# racer.net
KiCad netlist of a schematic drawn in Altium Designer
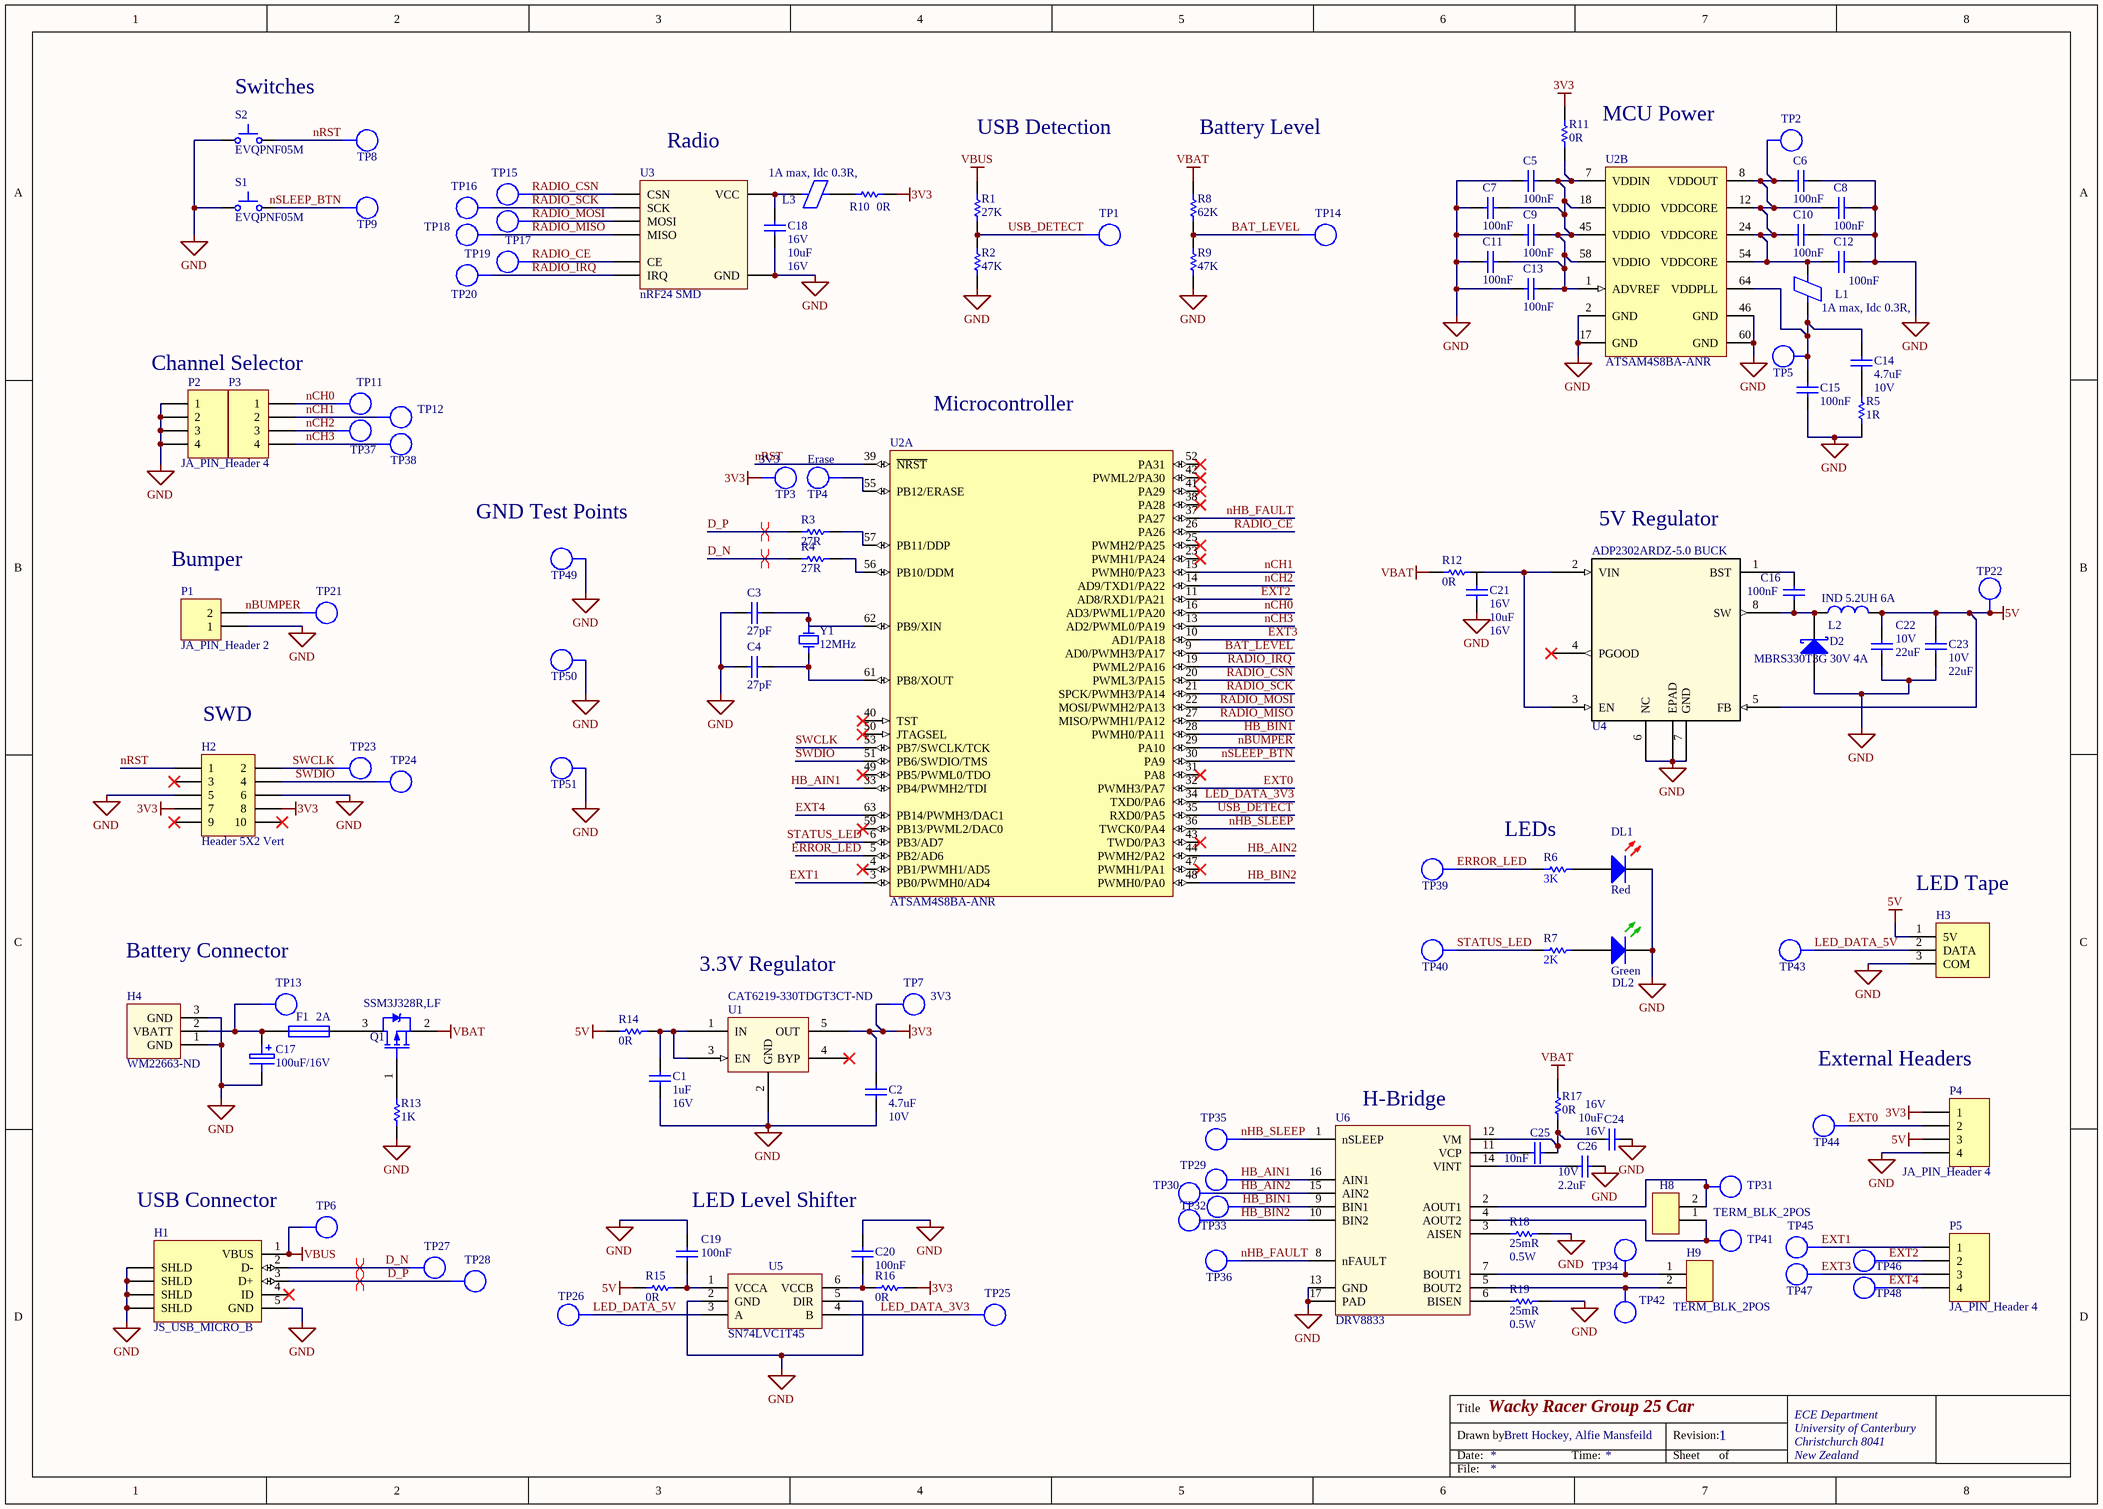
[diagram p0: racer.SchDoc]

(export (version "E")
  (design (tool "Eeschema 10.0.6"))
  (components
    (comp (ref "C1")
      (value "1uF")
      (footprint "CAPC1608L")
      (description "CAP CER 1uF Y5V -20% +80% 16V 0603")
      (fields (field (name "MAX VOLTAGE") "16V"))
      (libsource (lib "ECE AD19Components_22V1") (part "CC_1uF_0603"))
    )
    (comp (ref "C2")
      (value "4.7uF")
      (footprint "CAPC1608N")
      (description "CAP CER 4.7uF X5R +-20%  10V 0603")
      (fields (field (name "MAX VOLTAGE") "10V"))
      (libsource (lib "ECE AD19Components_22V1") (part "CC_4.7uF_0603"))
    )
    (comp (ref "C3")
      (value "27pF")
      (footprint "CAPC1608L")
      (description "CAP CER 27pF NPO/COG +-5% 50V 0603")
      (libsource (lib "ECE AD19Components_22V1") (part "CC_27pF_0603"))
    )
    (comp (ref "C4")
      (value "27pF")
      (footprint "CAPC1608L")
      (description "CAP CER 27pF NPO/COG +-5% 50V 0603")
      (libsource (lib "ECE AD19Components_22V1") (part "CC_27pF_0603"))
    )
    (comp (ref "C5")
      (value "100nF")
      (footprint "CAPC1608L")
      (description "CAP CER 100nF X7R +-10% 50V 0603")
      (libsource (lib "ECE AD19Components_22V1") (part "CC_100nF_0603"))
    )
    (comp (ref "C6")
      (value "100nF")
      (footprint "CAPC1608L")
      (description "CAP CER 100nF X7R +-10% 50V 0603")
      (libsource (lib "ECE AD19Components_22V1") (part "CC_100nF_0603"))
    )
    (comp (ref "C7")
      (value "100nF")
      (footprint "CAPC1608L")
      (description "CAP CER 100nF X7R +-10% 50V 0603")
      (libsource (lib "ECE AD19Components_22V1") (part "CC_100nF_0603"))
    )
    (comp (ref "C8")
      (value "100nF")
      (footprint "CAPC1608L")
      (description "CAP CER 100nF X7R +-10% 50V 0603")
      (libsource (lib "ECE AD19Components_22V1") (part "CC_100nF_0603"))
    )
    (comp (ref "C9")
      (value "100nF")
      (footprint "CAPC1608L")
      (description "CAP CER 100nF X7R +-10% 50V 0603")
      (libsource (lib "ECE AD19Components_22V1") (part "CC_100nF_0603"))
    )
    (comp (ref "C10")
      (value "100nF")
      (footprint "CAPC1608L")
      (description "CAP CER 100nF X7R +-10% 50V 0603")
      (libsource (lib "ECE AD19Components_22V1") (part "CC_100nF_0603"))
    )
    (comp (ref "C11")
      (value "100nF")
      (footprint "CAPC1608L")
      (description "CAP CER 100nF X7R +-10% 50V 0603")
      (libsource (lib "ECE AD19Components_22V1") (part "CC_100nF_0603"))
    )
    (comp (ref "C12")
      (value "100nF")
      (footprint "CAPC1608L")
      (description "CAP CER 100nF X7R +-10% 50V 0603")
      (libsource (lib "ECE AD19Components_22V1") (part "CC_100nF_0603"))
    )
    (comp (ref "C13")
      (value "100nF")
      (footprint "CAPC1608L")
      (description "CAP CER 100nF X7R +-10% 50V 0603")
      (libsource (lib "ECE AD19Components_22V1") (part "CC_100nF_0603"))
    )
    (comp (ref "C14")
      (value "4.7uF")
      (footprint "CAPC1608N")
      (description "CAP CER 4.7uF X5R +-20%  10V 0603")
      (fields (field (name "MAX VOLTAGE") "10V"))
      (libsource (lib "ECE AD19Components_22V1") (part "CC_4.7uF_0603"))
    )
    (comp (ref "C15")
      (value "100nF")
      (footprint "CAPC1608L")
      (description "CAP CER 100nF X7R +-10% 50V 0603")
      (libsource (lib "ECE AD19Components_22V1") (part "CC_100nF_0603"))
    )
    (comp (ref "C16")
      (value "100nF")
      (footprint "CAPC1608L")
      (description "CAP CER 100nF X7R +-10% 50V 0603")
      (libsource (lib "ECE AD19Components_22V1") (part "CC_100nF_0603"))
    )
    (comp (ref "C17")
      (value "100uF/16V")
      (footprint "NICH-1")
      (description "CAP ALUM 100uF 16V SMD")
      (fields (field (name "MANUFACTURER") "Nichcon"))
      (libsource (lib "ECE AD19Components_22V1") (part "CA_100uF_16V"))
    )
    (comp (ref "C18")
      (value "10uF")
      (footprint "CAPC2012L")
      (description "CAP CER 10uF X5R 16V 0805")
      (fields
        (field (name "MANUFACTURER") "Samsung Electro-Mechanics")
        (field (name "MANUFACTURER PART NUMBER") "CL21A106KOQNNWE")
        (field (name "VOLTAGE - RATED") "16V")
        (field (name "MAX VOLTAGE") "16V")
      )
      (libsource (lib "ECE AD19Components_22V1") (part "CC_10uF_0805_16V"))
    )
    (comp (ref "C19")
      (value "100nF")
      (footprint "CAPC1608L")
      (description "CAP CER 100nF X7R +-10% 50V 0603")
      (libsource (lib "ECE AD19Components_22V1") (part "CC_100nF_0603"))
    )
    (comp (ref "C20")
      (value "100nF")
      (footprint "CAPC1608L")
      (description "CAP CER 100nF X7R +-10% 50V 0603")
      (libsource (lib "ECE AD19Components_22V1") (part "CC_100nF_0603"))
    )
    (comp (ref "C21")
      (value "10uF")
      (footprint "CAPC2012L")
      (description "CAP CER 10uF X5R 16V 0805")
      (fields
        (field (name "MANUFACTURER") "Samsung Electro-Mechanics")
        (field (name "MANUFACTURER PART NUMBER") "CL21A106KOQNNWE")
        (field (name "VOLTAGE - RATED") "16V")
        (field (name "MAX VOLTAGE") "16V")
      )
      (libsource (lib "ECE AD19Components_22V1") (part "CC_10uF_0805_16V"))
    )
    (comp (ref "C22")
      (value "22uF")
      (footprint "CAPC3216L")
      (description "CAP CER 22uF Y5V -20% +80% 10V 1206")
      (fields (field (name "MAX VOLTAGE") "10V"))
      (libsource (lib "ECE AD19Components_22V1") (part "CC_22uF_1206"))
    )
    (comp (ref "C23")
      (value "22uF")
      (footprint "CAPC3216L")
      (description "CAP CER 22uF Y5V -20% +80% 10V 1206")
      (fields (field (name "MAX VOLTAGE") "10V"))
      (libsource (lib "ECE AD19Components_22V1") (part "CC_22uF_1206"))
    )
    (comp (ref "C24")
      (value "10uF")
      (footprint "CAPC2012L")
      (description "CAP CER 10uF X5R 16V 0805")
      (fields
        (field (name "MANUFACTURER") "Samsung Electro-Mechanics")
        (field (name "MANUFACTURER PART NUMBER") "CL21A106KOQNNWE")
        (field (name "VOLTAGE - RATED") "16V")
        (field (name "MAX VOLTAGE") "16V")
      )
      (libsource (lib "ECE AD19Components_22V1") (part "CC_10uF_0805_16V"))
    )
    (comp (ref "C25")
      (value "10nF")
      (footprint "CAPC1608L")
      (description "CAP CER 10nF X7R +-10% 50V 0603")
      (fields (field (name "Comment") "16V (minimum)"))
      (libsource (lib "ECE AD19Components_22V1") (part "CC_10nF_0603"))
    )
    (comp (ref "C26")
      (value "2.2uF")
      (footprint "CAPC1608L")
      (description "CAP CER 2.2uF X5R +-20% 10V 0603")
      (fields (field (name "MAX VOLTAGE") "10V"))
      (libsource (lib "ECE AD19Components_22V1") (part "CC_2.2uF_0603"))
    )
    (comp (ref "D2")
      (value "MBRS330T3G 30V 4A")
      (footprint "SMC")
      (description "SCHOTTKY  30V 4A")
      (fields
        (field (name "MANUFACTURER") "ON Semiconductor")
        (field (name "MANUFACTURER PART NUMBER") "MBRS330T3G")
      )
      (libsource (lib "ENCE461AD19_V22") (part "MBRS330T3G"))
    )
    (comp (ref "DL1")
      (value "Red")
      (footprint "WL-SMCW0603")
      (description "LED Red 250mcd 0603 SMD")
      (fields
        (field (name "MANUFACTURER") "WURTH ELEKTRONIK")
        (field (name "MANUFACTURER PART NUMBER") "150060RS75000")
        (field (name "LED COLOUR") "Red")
      )
      (libsource (lib "ECE AD19Components_22V1") (part "DL_150060RS75000"))
    )
    (comp (ref "DL2")
      (value "Green")
      (footprint "WL-SMCW0603")
      (description "LED Green 430mcd 0603 SMD")
      (fields
        (field (name "MANUFACTURER") "WURTH ELEKTRONIK")
        (field (name "MANUFACTURER PART NUMBER") "150060GS75000")
        (field (name "LED COLOUR") "Green")
      )
      (libsource (lib "ECE AD19Components_22V1") (part "DL_150060GS75000"))
    )
    (comp (ref "F1")
      (value "2A")
      (footprint "RESC3216N")
      (description "Fuse 2.0A Very Fast Acting 1206 SMD")
      (fields
        (field (name "MANUFACTURER") "MULTICOMP")
        (field (name "MANUFACTURER PART NUMBER") "MC12CF 002")
      )
      (libsource (lib "ECE AD19Components_22V1") (part "FS_Fuse_2.0A"))
    )
    (comp (ref "H1")
      (value "JS_USB_MICRO_B")
      (footprint "FCI_USB_10118194-0001LF")
      (description "CONN USB MICRO B RECPT SMT R/A")
      (fields (field (name "MANUFACTURER") "FCI") (field (name "MANUFACTURER PART NUMBER") "10118194-0001LF"))
      (libsource (lib "ECE AD19Components_22V1") (part "JS_USB_MICRO_B_SMT"))
    )
    (comp (ref "H2")
      (value "Header 5X2 Vert")
      (footprint "IDC2.54-V10D")
      (description "IDC Header, 2,54mm, 10-Pin, Vert")
      (libsource (lib "ECE AD19Components_22V1") (part "JA_HDR_IDC_5X2_VERT"))
    )
    (comp (ref "H3")
      (value "3 Pin Molex KK Hdr")
      (footprint "MOLEX_KK_3_HDR")
      (description "CONN HEADER 3POS 2.54mm VERT_Thru Hole")
      (fields (field (name "MANUFACTURER") "Molex"))
      (libsource (lib "ENCE461AD19_V22") (part "LED_Strip_Header"))
    )
    (comp (ref "H4")
      (value "Battery_HEADER_3pin")
      (footprint "BATT_HEADER_3POS")
      (description "3Pin Header 2.54mm spacing\r\nDigikey #WM22663-ND")
      (fields (field (name "SUPPLIER PART NUMBER 1") "WM22663-ND"))
      (libsource (lib "ENCE461AD19_V22") (part "Battery_HEADER_3pin"))
    )
    (comp (ref "H8")
      (value "TERM_BLK_2POS")
      (footprint "TERM_BLK_2POS")
      (description "2 Position Terminal Block 7.62mm spacing")
      (libsource (lib "") (part "TERM_BLK_2POS_1"))
    )
    (comp (ref "H9")
      (value "TERM_BLK_2POS")
      (footprint "TERM_BLK_2POS")
      (description "2 Position Terminal Block 7.62mm spacing")
      (libsource (lib "ENCE461AD19_V22") (part "TERM_BLK_2POS"))
    )
    (comp (ref "L1")
      (value "1A max, Idc 0.3R,")
      (footprint "INDC3216L")
      (description "Ferrite Bead, Rdc 0.3R, Z100MHZ 600R, Imax 1A, SMD 1206")
      (fields
        (field (name "MANUFACTURER") "FAIR-RITE")
        (field (name "MANUFACTURER PART NUMBER") "2512066017Y1")
      )
      (libsource (lib "ECE AD19Components_22V1") (part "IN_Ferrite-Bead"))
    )
    (comp (ref "L2")
      (value "IND 5.2UH 6A")
      (footprint "INDUCTOR5u2")
      (description "FIXED IND 5.2UH 6A 22 MOHM SMD")
      (fields
        (field (name "MANUFACTURER") "Sumida America Components Inc.")
        (field (name "MANUFACTURER PART NUMBER") "CDRH104RNP-5R2NC")
      )
      (libsource (lib "ENCE461AD19_V22") (part "CDRH104RNP-5R2NC"))
    )
    (comp (ref "L3")
      (value "1A max, Idc 0.3R,")
      (footprint "INDC3216L")
      (description "Ferrite Bead, Rdc 0.3R, Z100MHZ 600R, Imax 1A, SMD 1206")
      (fields
        (field (name "MANUFACTURER") "FAIR-RITE")
        (field (name "MANUFACTURER PART NUMBER") "2512066017Y1")
      )
      (libsource (lib "ECE AD19Components_22V1") (part "IN_Ferrite-Bead"))
    )
    (comp (ref "P1")
      (value "JA_PIN_Header 2")
      (footprint "HDR1X2")
      (description "Header, 2-Pin")
      (fields (field (name "PUBLISHER") "Altium Limited"))
      (libsource (lib "ECE AD19Components_22V1") (part "JA_PIN_Header 2"))
    )
    (comp (ref "P2")
      (value "JA_PIN_Header 4")
      (footprint "HDR1X4")
      (description "Header, 4-Pin")
      (fields (field (name "PUBLISHER") "Altium Limited"))
      (libsource (lib "ECE AD19Components_22V1") (part "JA_PIN_Header 4"))
    )
    (comp (ref "P3")
      (value "JA_PIN_Header 4")
      (footprint "HDR1X4")
      (description "Header, 4-Pin")
      (fields (field (name "PUBLISHER") "Altium Limited"))
      (libsource (lib "") (part "JA_PIN_Header 4_1"))
    )
    (comp (ref "P4")
      (value "JA_PIN_Header 4")
      (footprint "HDR1X4")
      (description "Header, 4-Pin")
      (fields (field (name "PUBLISHER") "Altium Limited"))
      (libsource (lib "ECE AD19Components_22V1") (part "JA_PIN_Header 4"))
    )
    (comp (ref "P5")
      (value "JA_PIN_Header 4")
      (footprint "HDR1X4")
      (description "Header, 4-Pin")
      (fields (field (name "PUBLISHER") "Altium Limited"))
      (libsource (lib "ECE AD19Components_22V1") (part "JA_PIN_Header 4"))
    )
    (comp (ref "Q1")
      (value "SSM3J328R,LF")
      (footprint "SOT23_L")
      (description "MOSFET P-CH 20V 6A SOT23-3")
      (fields
        (field (name "MANUFACTURER") "Toshiba")
        (field (name "MANUFACTURER PART NUMBER") "SSM3J328R,LF")
      )
      (libsource (lib "ECE AD19Components_22V1") (part "TM_SSM3J328R"))
    )
    (comp (ref "R1")
      (value "27K")
      (footprint "RESC1608L")
      (description "RES 27K OHM 1/10W 5% 0603 SMD")
      (libsource (lib "ECE AD19Components_22V1") (part "RS_27K"))
    )
    (comp (ref "R2")
      (value "47K")
      (footprint "RESC1608N")
      (description "RES 47.0K OHM 1/10W 5% 0603 SMD")
      (libsource (lib "ECE AD19Components_22V1") (part "RS_47K"))
    )
    (comp (ref "R3")
      (value "27R")
      (footprint "RESC1608L")
      (description "RES 27 OHM 1/10W 5% 0603 SMD")
      (libsource (lib "ECE AD19Components_22V1") (part "RS_27R"))
    )
    (comp (ref "R4")
      (value "27R")
      (footprint "RESC1608L")
      (description "RES 27 OHM 1/10W 5% 0603 SMD")
      (libsource (lib "ECE AD19Components_22V1") (part "RS_27R"))
    )
    (comp (ref "R5")
      (value "1R")
      (footprint "RESC3216L")
      (description "RES 1R OHM 1/4W 5% 1206 SMD")
      (libsource (lib "ECE AD19Components_22V1") (part "RT_1R"))
    )
    (comp (ref "R6")
      (value "3K")
      (footprint "RESC1608L")
      (description "RES 3K OHM 1/10W 5% 0603 SMD")
      (libsource (lib "ECE AD19Components_22V1") (part "RS_3K"))
    )
    (comp (ref "R7")
      (value "2K")
      (footprint "RESC1608L")
      (description "RES 2K OHM 1/10W 5% 0603 SMD")
      (libsource (lib "ECE AD19Components_22V1") (part "RS_2K"))
    )
    (comp (ref "R8")
      (value "62K")
      (footprint "RESC1608L")
      (description "RES 62.0K OHM 1/10W 5% 0603 SMD")
      (libsource (lib "ECE AD19Components_22V1") (part "RS_62K"))
    )
    (comp (ref "R9")
      (value "47K")
      (footprint "RESC1608N")
      (description "RES 47.0K OHM 1/10W 5% 0603 SMD")
      (libsource (lib "ECE AD19Components_22V1") (part "RS_47K"))
    )
    (comp (ref "R10")
      (value "0R")
      (footprint "RESC1608L")
      (description "RES 0.0 OHM 1/10W 5% 0603 SMD")
      (libsource (lib "ECE AD19Components_22V1") (part "RS_0R0"))
    )
    (comp (ref "R11")
      (value "0R")
      (footprint "RESC1608L")
      (description "RES 0.0 OHM 1/10W 5% 0603 SMD")
      (libsource (lib "ECE AD19Components_22V1") (part "RS_0R0"))
    )
    (comp (ref "R12")
      (value "0R")
      (footprint "RESC1608L")
      (description "RES 0.0 OHM 1/10W 5% 0603 SMD")
      (libsource (lib "ECE AD19Components_22V1") (part "RS_0R0"))
    )
    (comp (ref "R13")
      (value "1K")
      (footprint "RESC1608L")
      (description "RES 1.0K OHM 1/10W 5% 0603 SMD")
      (libsource (lib "ECE AD19Components_22V1") (part "RS_1K"))
    )
    (comp (ref "R14")
      (value "0R")
      (footprint "RESC1608L")
      (description "RES 0.0 OHM 1/10W 5% 0603 SMD")
      (libsource (lib "ECE AD19Components_22V1") (part "RS_0R0"))
    )
    (comp (ref "R15")
      (value "0R")
      (footprint "RESC1608L")
      (description "RES 0.0 OHM 1/10W 5% 0603 SMD")
      (libsource (lib "ECE AD19Components_22V1") (part "RS_0R0"))
    )
    (comp (ref "R16")
      (value "0R")
      (footprint "RESC1608L")
      (description "RES 0.0 OHM 1/10W 5% 0603 SMD")
      (libsource (lib "ECE AD19Components_22V1") (part "RS_0R0"))
    )
    (comp (ref "R17")
      (value "0R")
      (footprint "RESC1608L")
      (description "RES 0.0 OHM 1/10W 5% 0603 SMD")
      (libsource (lib "ECE AD19Components_22V1") (part "RS_0R0"))
    )
    (comp (ref "R18")
      (value "25mR")
      (footprint "RESC3216N")
      (description "0.5W 1206 25mR Resistor")
      (fields (field (name "POWER") "0.5W"))
      (libsource (lib "ENCE461AD19_V22") (part "RS_25mR"))
    )
    (comp (ref "R19")
      (value "25mR")
      (footprint "RESC3216N")
      (description "0.5W 1206 25mR Resistor")
      (fields (field (name "POWER") "0.5W"))
      (libsource (lib "ENCE461AD19_V22") (part "RS_25mR"))
    )
    (comp (ref "S1")
      (value "EVQPNF05M")
      (footprint "EVQPNF05M")
      (description "Panasonic 6 x 3.5mm SMD Light Touch Switch Type SMD")
      (fields (field (name "MANUFACTURER") "Panasonic"))
      (libsource (lib "ECE AD19Components_22V1") (part "WS_EVQPNF05M"))
    )
    (comp (ref "S2")
      (value "EVQPNF05M")
      (footprint "EVQPNF05M")
      (description "Panasonic 6 x 3.5mm SMD Light Touch Switch Type SMD")
      (fields (field (name "MANUFACTURER") "Panasonic"))
      (libsource (lib "ECE AD19Components_22V1") (part "WS_EVQPNF05M"))
    )
    (comp (ref "TP1")
      (value "3V3")
      (footprint "TP_0603")
      (description "Test-Point 3.3x1.6x2.1mm SMD")
      (fields
        (field (name "MANUFACTURER") "Harwin Inc")
        (field (name "MANUFACTURER PART NUMBER") "S1751-46R")
      )
      (libsource (lib "") (part "TP_1206_1"))
    )
    (comp (ref "TP2")
      (value "3V3")
      (footprint "TP_0603")
      (description "Test-Point 3.3x1.6x2.1mm SMD")
      (fields
        (field (name "MANUFACTURER") "Harwin Inc")
        (field (name "MANUFACTURER PART NUMBER") "S1751-46R")
      )
      (libsource (lib "") (part "TP_1206_1"))
    )
    (comp (ref "TP3")
      (value "3V3")
      (footprint "TP_0603")
      (description "Test-Point 3.3x1.6x2.1mm SMD")
      (fields
        (field (name "MANUFACTURER") "Harwin Inc")
        (field (name "MANUFACTURER PART NUMBER") "S1751-46R")
      )
      (libsource (lib "") (part "TP_1206_1"))
    )
    (comp (ref "TP4")
      (value "Erase")
      (footprint "TP_0603")
      (description "Test-Point 3.3x1.6x2.1mm SMD")
      (fields
        (field (name "MANUFACTURER") "Harwin Inc")
        (field (name "MANUFACTURER PART NUMBER") "S1751-46R")
      )
      (libsource (lib "") (part "TP_1206_1"))
    )
    (comp (ref "TP5")
      (value "3V3")
      (footprint "TP_0603")
      (description "Test-Point 3.3x1.6x2.1mm SMD")
      (fields
        (field (name "MANUFACTURER") "Harwin Inc")
        (field (name "MANUFACTURER PART NUMBER") "S1751-46R")
      )
      (libsource (lib "") (part "TP_1206_1"))
    )
    (comp (ref "TP6")
      (value "3V3")
      (footprint "TP_0603")
      (description "Test-Point 3.3x1.6x2.1mm SMD")
      (fields
        (field (name "MANUFACTURER") "Harwin Inc")
        (field (name "MANUFACTURER PART NUMBER") "S1751-46R")
      )
      (libsource (lib "") (part "TP_1206_1"))
    )
    (comp (ref "TP7")
      (value "3V3")
      (footprint "TP_0603")
      (description "Test-Point 3.3x1.6x2.1mm SMD")
      (fields
        (field (name "MANUFACTURER") "Harwin Inc")
        (field (name "MANUFACTURER PART NUMBER") "S1751-46R")
      )
      (libsource (lib "") (part "TP_1206_1"))
    )
    (comp (ref "TP8")
      (value "TP")
      (footprint "TP_0603")
      (description "Test-Point 3.3x1.6x2.1mm SMD")
      (fields
        (field (name "MANUFACTURER") "Harwin Inc")
        (field (name "MANUFACTURER PART NUMBER") "S1751-46R")
      )
      (libsource (lib "") (part "TP_1206_1"))
    )
    (comp (ref "TP9")
      (value "TP")
      (footprint "TP_0603")
      (description "Test-Point 3.3x1.6x2.1mm SMD")
      (fields
        (field (name "MANUFACTURER") "Harwin Inc")
        (field (name "MANUFACTURER PART NUMBER") "S1751-46R")
      )
      (libsource (lib "") (part "TP_1206_1"))
    )
    (comp (ref "TP11")
      (value "3V3")
      (footprint "TP_0603")
      (description "Test-Point 3.3x1.6x2.1mm SMD")
      (fields
        (field (name "MANUFACTURER") "Harwin Inc")
        (field (name "MANUFACTURER PART NUMBER") "S1751-46R")
      )
      (libsource (lib "") (part "TP_1206_1"))
    )
    (comp (ref "TP12")
      (value "3V3")
      (footprint "TP_0603")
      (description "Test-Point 3.3x1.6x2.1mm SMD")
      (fields
        (field (name "MANUFACTURER") "Harwin Inc")
        (field (name "MANUFACTURER PART NUMBER") "S1751-46R")
      )
      (libsource (lib "") (part "TP_1206_1"))
    )
    (comp (ref "TP13")
      (value "3V3")
      (footprint "TP_0603")
      (description "Test-Point 3.3x1.6x2.1mm SMD")
      (fields
        (field (name "MANUFACTURER") "Harwin Inc")
        (field (name "MANUFACTURER PART NUMBER") "S1751-46R")
      )
      (libsource (lib "") (part "TP_1206_1"))
    )
    (comp (ref "TP14")
      (value "3V3")
      (footprint "TP_0603")
      (description "Test-Point 3.3x1.6x2.1mm SMD")
      (fields
        (field (name "MANUFACTURER") "Harwin Inc")
        (field (name "MANUFACTURER PART NUMBER") "S1751-46R")
      )
      (libsource (lib "") (part "TP_1206_1"))
    )
    (comp (ref "TP15")
      (value "3V3")
      (footprint "TP_0603")
      (description "Test-Point 3.3x1.6x2.1mm SMD")
      (fields
        (field (name "MANUFACTURER") "Harwin Inc")
        (field (name "MANUFACTURER PART NUMBER") "S1751-46R")
      )
      (libsource (lib "ECE AD19Components_22V1") (part "TP_1206"))
    )
    (comp (ref "TP16")
      (value "3V3")
      (footprint "TP_0603")
      (description "Test-Point 3.3x1.6x2.1mm SMD")
      (fields
        (field (name "MANUFACTURER") "Harwin Inc")
        (field (name "MANUFACTURER PART NUMBER") "S1751-46R")
      )
      (libsource (lib "ECE AD19Components_22V1") (part "TP_1206"))
    )
    (comp (ref "TP17")
      (value "3V3")
      (footprint "TP_0603")
      (description "Test-Point 3.3x1.6x2.1mm SMD")
      (fields
        (field (name "MANUFACTURER") "Harwin Inc")
        (field (name "MANUFACTURER PART NUMBER") "S1751-46R")
      )
      (libsource (lib "ECE AD19Components_22V1") (part "TP_1206"))
    )
    (comp (ref "TP18")
      (value "3V3")
      (footprint "TP_0603")
      (description "Test-Point 3.3x1.6x2.1mm SMD")
      (fields
        (field (name "MANUFACTURER") "Harwin Inc")
        (field (name "MANUFACTURER PART NUMBER") "S1751-46R")
      )
      (libsource (lib "ECE AD19Components_22V1") (part "TP_1206"))
    )
    (comp (ref "TP19")
      (value "3V3")
      (footprint "TP_0603")
      (description "Test-Point 3.3x1.6x2.1mm SMD")
      (fields
        (field (name "MANUFACTURER") "Harwin Inc")
        (field (name "MANUFACTURER PART NUMBER") "S1751-46R")
      )
      (libsource (lib "ECE AD19Components_22V1") (part "TP_1206"))
    )
    (comp (ref "TP20")
      (value "3V3")
      (footprint "TP_0603")
      (description "Test-Point 3.3x1.6x2.1mm SMD")
      (fields
        (field (name "MANUFACTURER") "Harwin Inc")
        (field (name "MANUFACTURER PART NUMBER") "S1751-46R")
      )
      (libsource (lib "ECE AD19Components_22V1") (part "TP_1206"))
    )
    (comp (ref "TP21")
      (value "3V3")
      (footprint "TP_0603")
      (description "Test-Point 3.3x1.6x2.1mm SMD")
      (fields
        (field (name "MANUFACTURER") "Harwin Inc")
        (field (name "MANUFACTURER PART NUMBER") "S1751-46R")
      )
      (libsource (lib "") (part "TP_1206_1"))
    )
    (comp (ref "TP22")
      (value "3V3")
      (footprint "TP_0603")
      (description "Test-Point 3.3x1.6x2.1mm SMD")
      (fields
        (field (name "MANUFACTURER") "Harwin Inc")
        (field (name "MANUFACTURER PART NUMBER") "S1751-46R")
      )
      (libsource (lib "") (part "TP_1206_1"))
    )
    (comp (ref "TP23")
      (value "3V3")
      (footprint "TP_0603")
      (description "Test-Point 3.3x1.6x2.1mm SMD")
      (fields
        (field (name "MANUFACTURER") "Harwin Inc")
        (field (name "MANUFACTURER PART NUMBER") "S1751-46R")
      )
      (libsource (lib "") (part "TP_1206_1"))
    )
    (comp (ref "TP24")
      (value "3V3")
      (footprint "TP_0603")
      (description "Test-Point 3.3x1.6x2.1mm SMD")
      (fields
        (field (name "MANUFACTURER") "Harwin Inc")
        (field (name "MANUFACTURER PART NUMBER") "S1751-46R")
      )
      (libsource (lib "") (part "TP_1206_1"))
    )
    (comp (ref "TP25")
      (value "3V3")
      (footprint "TP_0603")
      (description "Test-Point 3.3x1.6x2.1mm SMD")
      (fields
        (field (name "MANUFACTURER") "Harwin Inc")
        (field (name "MANUFACTURER PART NUMBER") "S1751-46R")
      )
      (libsource (lib "") (part "TP_1206_1"))
    )
    (comp (ref "TP26")
      (value "3V3")
      (footprint "TP_0603")
      (description "Test-Point 3.3x1.6x2.1mm SMD")
      (fields
        (field (name "MANUFACTURER") "Harwin Inc")
        (field (name "MANUFACTURER PART NUMBER") "S1751-46R")
      )
      (libsource (lib "ECE AD19Components_22V1") (part "TP_1206"))
    )
    (comp (ref "TP27")
      (value "3V3")
      (footprint "TP_0603")
      (description "Test-Point 3.3x1.6x2.1mm SMD")
      (fields
        (field (name "MANUFACTURER") "Harwin Inc")
        (field (name "MANUFACTURER PART NUMBER") "S1751-46R")
      )
      (libsource (lib "") (part "TP_1206_1"))
    )
    (comp (ref "TP28")
      (value "3V3")
      (footprint "TP_0603")
      (description "Test-Point 3.3x1.6x2.1mm SMD")
      (fields
        (field (name "MANUFACTURER") "Harwin Inc")
        (field (name "MANUFACTURER PART NUMBER") "S1751-46R")
      )
      (libsource (lib "") (part "TP_1206_1"))
    )
    (comp (ref "TP29")
      (value "TP")
      (footprint "TP_0603")
      (description "Test-Point 3.3x1.6x2.1mm SMD")
      (fields
        (field (name "MANUFACTURER") "Harwin Inc")
        (field (name "MANUFACTURER PART NUMBER") "S1751-46R")
      )
      (libsource (lib "") (part "TP_1206_1"))
    )
    (comp (ref "TP30")
      (value "TP")
      (footprint "TP_0603")
      (description "Test-Point 3.3x1.6x2.1mm SMD")
      (fields
        (field (name "MANUFACTURER") "Harwin Inc")
        (field (name "MANUFACTURER PART NUMBER") "S1751-46R")
      )
      (libsource (lib "") (part "TP_1206_1"))
    )
    (comp (ref "TP31")
      (value "TP")
      (footprint "TP_0603")
      (description "Test-Point 3.3x1.6x2.1mm SMD")
      (fields
        (field (name "MANUFACTURER") "Harwin Inc")
        (field (name "MANUFACTURER PART NUMBER") "S1751-46R")
      )
      (libsource (lib "") (part "TP_1206_1"))
    )
    (comp (ref "TP32")
      (value "TP")
      (footprint "TP_0603")
      (description "Test-Point 3.3x1.6x2.1mm SMD")
      (fields
        (field (name "MANUFACTURER") "Harwin Inc")
        (field (name "MANUFACTURER PART NUMBER") "S1751-46R")
      )
      (libsource (lib "") (part "TP_1206_1"))
    )
    (comp (ref "TP33")
      (value "TP")
      (footprint "TP_0603")
      (description "Test-Point 3.3x1.6x2.1mm SMD")
      (fields
        (field (name "MANUFACTURER") "Harwin Inc")
        (field (name "MANUFACTURER PART NUMBER") "S1751-46R")
      )
      (libsource (lib "") (part "TP_1206_1"))
    )
    (comp (ref "TP34")
      (value "TP")
      (footprint "TP_0603")
      (description "Test-Point 3.3x1.6x2.1mm SMD")
      (fields
        (field (name "MANUFACTURER") "Harwin Inc")
        (field (name "MANUFACTURER PART NUMBER") "S1751-46R")
      )
      (libsource (lib "") (part "TP_1206_1"))
    )
    (comp (ref "TP35")
      (value "TP")
      (footprint "TP_0603")
      (description "Test-Point 3.3x1.6x2.1mm SMD")
      (fields
        (field (name "MANUFACTURER") "Harwin Inc")
        (field (name "MANUFACTURER PART NUMBER") "S1751-46R")
      )
      (libsource (lib "") (part "TP_1206_1"))
    )
    (comp (ref "TP36")
      (value "TP")
      (footprint "TP_0603")
      (description "Test-Point 3.3x1.6x2.1mm SMD")
      (fields
        (field (name "MANUFACTURER") "Harwin Inc")
        (field (name "MANUFACTURER PART NUMBER") "S1751-46R")
      )
      (libsource (lib "") (part "TP_1206_1"))
    )
    (comp (ref "TP37")
      (value "3V3")
      (footprint "TP_0603")
      (description "Test-Point 3.3x1.6x2.1mm SMD")
      (fields
        (field (name "MANUFACTURER") "Harwin Inc")
        (field (name "MANUFACTURER PART NUMBER") "S1751-46R")
      )
      (libsource (lib "") (part "TP_1206_1"))
    )
    (comp (ref "TP38")
      (value "3V3")
      (footprint "TP_0603")
      (description "Test-Point 3.3x1.6x2.1mm SMD")
      (fields
        (field (name "MANUFACTURER") "Harwin Inc")
        (field (name "MANUFACTURER PART NUMBER") "S1751-46R")
      )
      (libsource (lib "") (part "TP_1206_1"))
    )
    (comp (ref "TP39")
      (value "3V3")
      (footprint "TP_0603")
      (description "Test-Point 3.3x1.6x2.1mm SMD")
      (fields
        (field (name "MANUFACTURER") "Harwin Inc")
        (field (name "MANUFACTURER PART NUMBER") "S1751-46R")
      )
      (libsource (lib "ECE AD19Components_22V1") (part "TP_1206"))
    )
    (comp (ref "TP40")
      (value "3V3")
      (footprint "TP_0603")
      (description "Test-Point 3.3x1.6x2.1mm SMD")
      (fields
        (field (name "MANUFACTURER") "Harwin Inc")
        (field (name "MANUFACTURER PART NUMBER") "S1751-46R")
      )
      (libsource (lib "ECE AD19Components_22V1") (part "TP_1206"))
    )
    (comp (ref "TP41")
      (value "TP")
      (footprint "TP_0603")
      (description "Test-Point 3.3x1.6x2.1mm SMD")
      (fields
        (field (name "MANUFACTURER") "Harwin Inc")
        (field (name "MANUFACTURER PART NUMBER") "S1751-46R")
      )
      (libsource (lib "") (part "TP_1206_1"))
    )
    (comp (ref "TP42")
      (value "TP")
      (footprint "TP_0603")
      (description "Test-Point 3.3x1.6x2.1mm SMD")
      (fields
        (field (name "MANUFACTURER") "Harwin Inc")
        (field (name "MANUFACTURER PART NUMBER") "S1751-46R")
      )
      (libsource (lib "") (part "TP_1206_1"))
    )
    (comp (ref "TP43")
      (value "3V3")
      (footprint "TP_0603")
      (description "Test-Point 3.3x1.6x2.1mm SMD")
      (fields
        (field (name "MANUFACTURER") "Harwin Inc")
        (field (name "MANUFACTURER PART NUMBER") "S1751-46R")
      )
      (libsource (lib "") (part "TP_1206_1"))
    )
    (comp (ref "TP44")
      (value "3V3")
      (footprint "TP_0603")
      (description "Test-Point 3.3x1.6x2.1mm SMD")
      (fields
        (field (name "MANUFACTURER") "Harwin Inc")
        (field (name "MANUFACTURER PART NUMBER") "S1751-46R")
      )
      (libsource (lib "") (part "TP_1206_1"))
    )
    (comp (ref "TP45")
      (value "3V3")
      (footprint "TP_0603")
      (description "Test-Point 3.3x1.6x2.1mm SMD")
      (fields
        (field (name "MANUFACTURER") "Harwin Inc")
        (field (name "MANUFACTURER PART NUMBER") "S1751-46R")
      )
      (libsource (lib "") (part "TP_1206_1"))
    )
    (comp (ref "TP46")
      (value "3V3")
      (footprint "TP_0603")
      (description "Test-Point 3.3x1.6x2.1mm SMD")
      (fields
        (field (name "MANUFACTURER") "Harwin Inc")
        (field (name "MANUFACTURER PART NUMBER") "S1751-46R")
      )
      (libsource (lib "") (part "TP_1206_1"))
    )
    (comp (ref "TP47")
      (value "3V3")
      (footprint "TP_0603")
      (description "Test-Point 3.3x1.6x2.1mm SMD")
      (fields
        (field (name "MANUFACTURER") "Harwin Inc")
        (field (name "MANUFACTURER PART NUMBER") "S1751-46R")
      )
      (libsource (lib "") (part "TP_1206_1"))
    )
    (comp (ref "TP48")
      (value "3V3")
      (footprint "TP_0603")
      (description "Test-Point 3.3x1.6x2.1mm SMD")
      (fields
        (field (name "MANUFACTURER") "Harwin Inc")
        (field (name "MANUFACTURER PART NUMBER") "S1751-46R")
      )
      (libsource (lib "") (part "TP_1206_1"))
    )
    (comp (ref "TP49")
      (value "TP")
      (footprint "TP_1206")
      (description "Test-Point 3.3x1.6x2.1mm SMD")
      (fields
        (field (name "MANUFACTURER") "Harwin Inc")
        (field (name "MANUFACTURER PART NUMBER") "S1751-46R")
      )
      (libsource (lib "") (part "TP_1206_1"))
    )
    (comp (ref "TP50")
      (value "TP")
      (footprint "TP_1206")
      (description "Test-Point 3.3x1.6x2.1mm SMD")
      (fields
        (field (name "MANUFACTURER") "Harwin Inc")
        (field (name "MANUFACTURER PART NUMBER") "S1751-46R")
      )
      (libsource (lib "") (part "TP_1206_1"))
    )
    (comp (ref "TP51")
      (value "TP")
      (footprint "TP_1206")
      (description "Test-Point 3.3x1.6x2.1mm SMD")
      (fields
        (field (name "MANUFACTURER") "Harwin Inc")
        (field (name "MANUFACTURER PART NUMBER") "S1751-46R")
      )
      (libsource (lib "") (part "TP_1206_1"))
    )
    (comp (ref "U1")
      (value "CAT6219-330TDGT3")
      (footprint "SOT95P280X145-5N")
      (description "IC REG LIN 3.3V 500MA TSOT23-5")
      (fields
        (field (name "BASE PART NUMBER") "CAT6219")
        (field (name "SUPPLIER PART NUMBER") "CAT6219-330TDGT3CT-ND")
      )
      (libsource (lib "ENCE461AD19_V22") (part "SV_CAT6219-330TDGT3"))
    )
    (comp (ref "U2")
      (value "ATSAM4S8BA-ANR")
      (footprint "LQFP64_L")
      (description "IC MCU 32BIT 512KB FLASH 64LQFP")
      (fields (field (name "MANUFACTURER") "Atmel"))
      (libsource (lib "ECE AD19Components_22V1") (part "SE_ATSAM4S16BA-MU"))
    )
    (comp (ref "U3")
      (value "nRF24 SMD")
      (footprint "NRF24")
      (description "nRF24 SMD Module")
      (libsource (lib "ENCE461AD19_V22") (part "NRF24"))
    )
    (comp (ref "U4")
      (value "ADP2302ARDZ-5.0 BUCK")
      (footprint "RD_8_1")
      (description "IC REG BUCK 5V 2A 8SOIC")
      (fields (field (name "MANUFACTURER_PART_NUMBER") "ADP2302ARDZ-5.0-R7"))
      (libsource (lib "ENCE461AD19_V22") (part "ADP2302ARDZ-5.0-R7"))
    )
    (comp (ref "U5")
      (value "SN74LVC1T45")
      (footprint "SOT23-6_N")
      (description "1.8V - 5V level converter")
      (libsource (lib "ENCE461AD19_V22") (part "SN74LVC1T45"))
    )
    (comp (ref "U6")
      (value "DRV8833")
      (footprint "HTSOP16 DRV8833")
      (description "Dual H-Bridge Motor Driver 1.5A")
      (libsource (lib "ENCE461AD19_V22") (part "DRV8833"))
    )
    (comp (ref "Y1")
      (value "12MHz")
      (footprint "6.0X3.5-4")
      (description "CRYSTAL 12MHZ 18PF 6X3.5mm SMD")
      (fields
        (field (name "MANUFACTURER") "CTS-Frequency Controls")
        (field (name "MANUFACTURER PART NUMBER") "406C35D12M00000")
        (field (name "FREQUENCY") "12MHz")
      )
      (libsource (lib "ECE AD19Components_22V1") (part "XT_CRYSTAL_12MHz_18pF"))
    )
  )
  (nets
    (net (code "1") (name "/BAT_LEVEL") (class "Default")
      (node (ref "R8") (pin "1") (pinfunction "1_1") (pintype "passive"))
      (node (ref "R9") (pin "2") (pinfunction "2_2") (pintype "passive"))
      (node (ref "TP14") (pin "1") (pinfunction "1_1") (pintype "passive"))
      (node (ref "U2") (pin "9") (pinfunction "AD0/PWMH3/PA17_9") (pintype "bidirectional"))
    )
    (net (code "2") (name "/D_N") (class "Default")
      (node (ref "H1") (pin "2") (pinfunction "D-_2") (pintype "bidirectional"))
      (node (ref "R4") (pin "1") (pinfunction "1_1") (pintype "passive"))
      (node (ref "TP27") (pin "1") (pinfunction "1_1") (pintype "passive"))
    )
    (net (code "3") (name "/D_P") (class "Default")
      (node (ref "H1") (pin "3") (pinfunction "D+_3") (pintype "bidirectional"))
      (node (ref "R3") (pin "1") (pinfunction "1_1") (pintype "passive"))
      (node (ref "TP28") (pin "1") (pinfunction "1_1") (pintype "passive"))
    )
    (net (code "4") (name "/ERROR_LED") (class "Default")
      (node (ref "R6") (pin "1") (pinfunction "1_1") (pintype "passive"))
      (node (ref "TP39") (pin "1") (pinfunction "1_1") (pintype "passive"))
      (node (ref "U2") (pin "5") (pinfunction "PB2/AD6_5") (pintype "bidirectional"))
    )
    (net (code "5") (name "/EXT0") (class "Default")
      (node (ref "P4") (pin "2") (pinfunction "2_2") (pintype "passive"))
      (node (ref "TP44") (pin "1") (pinfunction "1_1") (pintype "passive"))
      (node (ref "U2") (pin "32") (pinfunction "PWMH3/PA7_32") (pintype "bidirectional"))
    )
    (net (code "6") (name "/EXT1") (class "Default")
      (node (ref "P5") (pin "1") (pinfunction "1_1") (pintype "passive"))
      (node (ref "TP45") (pin "1") (pinfunction "1_1") (pintype "passive"))
      (node (ref "U2") (pin "3") (pinfunction "PB0/PWMH0/AD4_3") (pintype "bidirectional"))
    )
    (net (code "7") (name "/EXT2") (class "Default")
      (node (ref "P5") (pin "2") (pinfunction "2_2") (pintype "passive"))
      (node (ref "TP46") (pin "1") (pinfunction "1_1") (pintype "passive"))
      (node (ref "U2") (pin "11") (pinfunction "AD8/RXD1/PA21_11") (pintype "bidirectional"))
    )
    (net (code "8") (name "/EXT3") (class "Default")
      (node (ref "P5") (pin "3") (pinfunction "3_3") (pintype "passive"))
      (node (ref "TP47") (pin "1") (pinfunction "1_1") (pintype "passive"))
      (node (ref "U2") (pin "10") (pinfunction "AD1/PA18_10") (pintype "bidirectional"))
    )
    (net (code "9") (name "/EXT4") (class "Default")
      (node (ref "P5") (pin "4") (pinfunction "4_4") (pintype "passive"))
      (node (ref "TP48") (pin "1") (pinfunction "1_1") (pintype "passive"))
      (node (ref "U2") (pin "63") (pinfunction "PB14/PWMH3/DAC1_63") (pintype "bidirectional"))
    )
    (net (code "10") (name "/HB_AIN1") (class "Default")
      (node (ref "TP29") (pin "1") (pinfunction "1_1") (pintype "passive"))
      (node (ref "U2") (pin "33") (pinfunction "PB4/PWMH2/TDI_33") (pintype "bidirectional"))
      (node (ref "U6") (pin "16") (pinfunction "AIN1_16") (pintype "passive"))
    )
    (net (code "11") (name "/HB_AIN2") (class "Default")
      (node (ref "TP30") (pin "1") (pinfunction "1_1") (pintype "passive"))
      (node (ref "U2") (pin "44") (pinfunction "PWMH2/PA2_44") (pintype "bidirectional"))
      (node (ref "U6") (pin "15") (pinfunction "AIN2_15") (pintype "passive"))
    )
    (net (code "12") (name "/HB_BIN1") (class "Default")
      (node (ref "TP32") (pin "1") (pinfunction "1_1") (pintype "passive"))
      (node (ref "U2") (pin "28") (pinfunction "PWMH0/PA11_28") (pintype "bidirectional"))
      (node (ref "U6") (pin "9") (pinfunction "BIN1_9") (pintype "passive"))
    )
    (net (code "13") (name "/HB_BIN2") (class "Default")
      (node (ref "TP33") (pin "1") (pinfunction "1_1") (pintype "passive"))
      (node (ref "U2") (pin "48") (pinfunction "PWMH0/PA0_48") (pintype "bidirectional"))
      (node (ref "U6") (pin "10") (pinfunction "BIN2_10") (pintype "passive"))
    )
    (net (code "14") (name "/LED_DATA_3V3") (class "Default")
      (node (ref "TP25") (pin "1") (pinfunction "1_1") (pintype "passive"))
      (node (ref "U2") (pin "34") (pinfunction "TXD0/PA6_34") (pintype "bidirectional"))
      (node (ref "U5") (pin "4") (pinfunction "B_4") (pintype "passive"))
    )
    (net (code "15") (name "/LED_DATA_5V") (class "Default")
      (node (ref "H3") (pin "2") (pinfunction "DATA_2") (pintype "passive"))
      (node (ref "TP26") (pin "1") (pinfunction "1_1") (pintype "passive"))
      (node (ref "TP43") (pin "1") (pinfunction "1_1") (pintype "passive"))
      (node (ref "U5") (pin "3") (pinfunction "A_3") (pintype "passive"))
    )
    (net (code "16") (name "/RADIO_CE") (class "Default")
      (node (ref "TP19") (pin "1") (pinfunction "1_1") (pintype "passive"))
      (node (ref "U2") (pin "26") (pinfunction "PA26_26") (pintype "bidirectional"))
      (node (ref "U3") (pin "3") (pinfunction "CE_3") (pintype "passive"))
    )
    (net (code "17") (name "/RADIO_CSN") (class "Default")
      (node (ref "TP15") (pin "1") (pinfunction "1_1") (pintype "passive"))
      (node (ref "U2") (pin "20") (pinfunction "PWML3/PA15_20") (pintype "bidirectional"))
      (node (ref "U3") (pin "4") (pinfunction "CSN_4") (pintype "passive"))
    )
    (net (code "18") (name "/RADIO_IRQ") (class "Default")
      (node (ref "TP20") (pin "1") (pinfunction "1_1") (pintype "passive"))
      (node (ref "U2") (pin "19") (pinfunction "PWML2/PA16_19") (pintype "bidirectional"))
      (node (ref "U3") (pin "8") (pinfunction "IRQ_8") (pintype "passive"))
    )
    (net (code "19") (name "/RADIO_MISO") (class "Default")
      (node (ref "TP18") (pin "1") (pinfunction "1_1") (pintype "passive"))
      (node (ref "U2") (pin "27") (pinfunction "MISO/PWMH1/PA12_27") (pintype "bidirectional"))
      (node (ref "U3") (pin "7") (pinfunction "MISO_7") (pintype "passive"))
    )
    (net (code "20") (name "/RADIO_MOSI") (class "Default")
      (node (ref "TP17") (pin "1") (pinfunction "1_1") (pintype "passive"))
      (node (ref "U2") (pin "22") (pinfunction "MOSI/PWMH2/PA13_22") (pintype "bidirectional"))
      (node (ref "U3") (pin "6") (pinfunction "MOSI_6") (pintype "passive"))
    )
    (net (code "21") (name "/RADIO_SCK") (class "Default")
      (node (ref "TP16") (pin "1") (pinfunction "1_1") (pintype "passive"))
      (node (ref "U2") (pin "21") (pinfunction "SPCK/PWMH3/PA14_21") (pintype "bidirectional"))
      (node (ref "U3") (pin "5") (pinfunction "SCK_5") (pintype "passive"))
    )
    (net (code "22") (name "/STATUS_LED") (class "Default")
      (node (ref "R7") (pin "1") (pinfunction "1_1") (pintype "passive"))
      (node (ref "TP40") (pin "1") (pinfunction "1_1") (pintype "passive"))
      (node (ref "U2") (pin "6") (pinfunction "PB3/AD7_6") (pintype "bidirectional"))
    )
    (net (code "23") (name "/SWCLK") (class "Default")
      (node (ref "H2") (pin "2") (pinfunction "2_2") (pintype "passive"))
      (node (ref "TP23") (pin "1") (pinfunction "1_1") (pintype "passive"))
      (node (ref "U2") (pin "53") (pinfunction "PB7/SWCLK/TCK_53") (pintype "bidirectional"))
    )
    (net (code "24") (name "/SWDIO") (class "Default")
      (node (ref "H2") (pin "4") (pinfunction "4_4") (pintype "passive"))
      (node (ref "TP24") (pin "1") (pinfunction "1_1") (pintype "passive"))
      (node (ref "U2") (pin "51") (pinfunction "PB6/SWDIO/TMS_51") (pintype "bidirectional"))
    )
    (net (code "25") (name "/USB_DETECT") (class "Default")
      (node (ref "R1") (pin "1") (pinfunction "1_1") (pintype "passive"))
      (node (ref "R2") (pin "2") (pinfunction "2_2") (pintype "passive"))
      (node (ref "TP1") (pin "1") (pinfunction "1_1") (pintype "passive"))
      (node (ref "U2") (pin "35") (pinfunction "RXD0/PA5_35") (pintype "bidirectional"))
    )
    (net (code "26") (name "/nBUMPER") (class "Default")
      (node (ref "P1") (pin "2") (pinfunction "2_2") (pintype "passive"))
      (node (ref "TP21") (pin "1") (pinfunction "1_1") (pintype "passive"))
      (node (ref "U2") (pin "29") (pinfunction "PA10_29") (pintype "bidirectional"))
    )
    (net (code "27") (name "/nCH0") (class "Default")
      (node (ref "P3") (pin "1") (pinfunction "1_1") (pintype "passive"))
      (node (ref "TP11") (pin "1") (pinfunction "1_1") (pintype "passive"))
      (node (ref "U2") (pin "16") (pinfunction "AD3/PWML1/PA20_16") (pintype "bidirectional"))
    )
    (net (code "28") (name "/nCH1") (class "Default")
      (node (ref "P3") (pin "2") (pinfunction "2_2") (pintype "passive"))
      (node (ref "TP12") (pin "1") (pinfunction "1_1") (pintype "passive"))
      (node (ref "U2") (pin "15") (pinfunction "PWMH0/PA23_15") (pintype "bidirectional"))
    )
    (net (code "29") (name "/nCH2") (class "Default")
      (node (ref "P3") (pin "3") (pinfunction "3_3") (pintype "passive"))
      (node (ref "TP37") (pin "1") (pinfunction "1_1") (pintype "passive"))
      (node (ref "U2") (pin "14") (pinfunction "AD9/TXD1/PA22_14") (pintype "bidirectional"))
    )
    (net (code "30") (name "/nCH3") (class "Default")
      (node (ref "P3") (pin "4") (pinfunction "4_4") (pintype "passive"))
      (node (ref "TP38") (pin "1") (pinfunction "1_1") (pintype "passive"))
      (node (ref "U2") (pin "13") (pinfunction "AD2/PWML0/PA19_13") (pintype "bidirectional"))
    )
    (net (code "31") (name "/nHB_FAULT") (class "Default")
      (node (ref "TP36") (pin "1") (pinfunction "1_1") (pintype "passive"))
      (node (ref "U2") (pin "37") (pinfunction "PA27_37") (pintype "bidirectional"))
      (node (ref "U6") (pin "8") (pinfunction "nFAULT_8") (pintype "passive"))
    )
    (net (code "32") (name "/nHB_SLEEP") (class "Default")
      (node (ref "TP35") (pin "1") (pinfunction "1_1") (pintype "passive"))
      (node (ref "U2") (pin "36") (pinfunction "TWCK0/PA4_36") (pintype "bidirectional"))
      (node (ref "U6") (pin "1") (pinfunction "nSLEEP_1") (pintype "passive"))
    )
    (net (code "33") (name "/nRST") (class "Default")
      (node (ref "H2") (pin "1") (pinfunction "1_1") (pintype "passive"))
      (node (ref "S2") (pin "2") (pintype "passive"))
      (node (ref "TP8") (pin "1") (pinfunction "1_1") (pintype "passive"))
      (node (ref "U2") (pin "39") (pinfunction "~{NRST}_39") (pintype "bidirectional"))
    )
    (net (code "34") (name "/nSLEEP_BTN") (class "Default")
      (node (ref "S1") (pin "2") (pintype "passive"))
      (node (ref "TP9") (pin "1") (pinfunction "1_1") (pintype "passive"))
      (node (ref "U2") (pin "30") (pinfunction "PA9_30") (pintype "bidirectional"))
    )
    (net (code "35") (name "3V3") (class "Default")
      (node (ref "C2") (pin "2") (pinfunction "2_2") (pintype "passive"))
      (node (ref "H2") (pin "7") (pinfunction "7_7") (pintype "passive"))
      (node (ref "H2") (pin "8") (pinfunction "8_8") (pintype "passive"))
      (node (ref "P4") (pin "1") (pinfunction "1_1") (pintype "passive"))
      (node (ref "R10") (pin "2") (pinfunction "2_2") (pintype "passive"))
      (node (ref "R11") (pin "2") (pinfunction "2_2") (pintype "passive"))
      (node (ref "R16") (pin "2") (pinfunction "2_2") (pintype "passive"))
      (node (ref "TP3") (pin "1") (pinfunction "1_1") (pintype "passive"))
      (node (ref "TP7") (pin "1") (pinfunction "1_1") (pintype "passive"))
      (node (ref "U1") (pin "5") (pinfunction "OUT_5") (pintype "power_in"))
    )
    (net (code "36") (name "5V") (class "Default")
      (node (ref "C22") (pin "2") (pinfunction "2_2") (pintype "passive"))
      (node (ref "C23") (pin "2") (pinfunction "2_2") (pintype "passive"))
      (node (ref "H3") (pin "1") (pinfunction "5V_1") (pintype "passive"))
      (node (ref "L2") (pin "2") (pintype "passive"))
      (node (ref "P4") (pin "3") (pinfunction "3_3") (pintype "passive"))
      (node (ref "R14") (pin "1") (pinfunction "1_1") (pintype "passive"))
      (node (ref "R15") (pin "1") (pinfunction "1_1") (pintype "passive"))
      (node (ref "TP22") (pin "1") (pinfunction "1_1") (pintype "passive"))
      (node (ref "U4") (pin "5") (pinfunction "FB_5") (pintype "input"))
    )
    (net (code "37") (name "GND") (class "Default")
      (node (ref "C1") (pin "1") (pinfunction "1_1") (pintype "passive"))
      (node (ref "C10") (pin "1") (pinfunction "1_1") (pintype "passive"))
      (node (ref "C11") (pin "1") (pinfunction "1_1") (pintype "passive"))
      (node (ref "C12") (pin "1") (pinfunction "1_1") (pintype "passive"))
      (node (ref "C13") (pin "1") (pinfunction "1_1") (pintype "passive"))
      (node (ref "C15") (pin "2") (pinfunction "2_2") (pintype "passive"))
      (node (ref "C17") (pin "1") (pintype "passive"))
      (node (ref "C18") (pin "1") (pinfunction "1_1") (pintype "passive"))
      (node (ref "C19") (pin "1") (pinfunction "1_1") (pintype "passive"))
      (node (ref "C2") (pin "1") (pinfunction "1_1") (pintype "passive"))
      (node (ref "C20") (pin "1") (pinfunction "1_1") (pintype "passive"))
      (node (ref "C21") (pin "1") (pinfunction "1_1") (pintype "passive"))
      (node (ref "C22") (pin "1") (pinfunction "1_1") (pintype "passive"))
      (node (ref "C23") (pin "1") (pinfunction "1_1") (pintype "passive"))
      (node (ref "C24") (pin "1") (pinfunction "1_1") (pintype "passive"))
      (node (ref "C26") (pin "2") (pinfunction "2_2") (pintype "passive"))
      (node (ref "C3") (pin "1") (pinfunction "1_1") (pintype "passive"))
      (node (ref "C4") (pin "1") (pinfunction "1_1") (pintype "passive"))
      (node (ref "C5") (pin "1") (pinfunction "1_1") (pintype "passive"))
      (node (ref "C6") (pin "1") (pinfunction "1_1") (pintype "passive"))
      (node (ref "C7") (pin "1") (pinfunction "1_1") (pintype "passive"))
      (node (ref "C8") (pin "1") (pinfunction "1_1") (pintype "passive"))
      (node (ref "C9") (pin "1") (pinfunction "1_1") (pintype "passive"))
      (node (ref "D2") (pin "1") (pinfunction "A_1") (pintype "passive"))
      (node (ref "DL1") (pin "1") (pinfunction "K_1") (pintype "passive"))
      (node (ref "DL2") (pin "1") (pinfunction "K_1") (pintype "passive"))
      (node (ref "H1") (pin "5") (pinfunction "GND_5") (pintype "passive"))
      (node (ref "H1") (pin "6") (pinfunction "SHLD_6") (pintype "passive"))
      (node (ref "H2") (pin "5") (pinfunction "5_5") (pintype "passive"))
      (node (ref "H2") (pin "6") (pinfunction "6_6") (pintype "passive"))
      (node (ref "H3") (pin "3") (pinfunction "COM_3") (pintype "passive"))
      (node (ref "H4") (pin "1") (pinfunction "GND_1") (pintype "passive"))
      (node (ref "H4") (pin "3") (pinfunction "GND_3") (pintype "passive"))
      (node (ref "P1") (pin "1") (pinfunction "1_1") (pintype "passive"))
      (node (ref "P2") (pin "1") (pinfunction "1_1") (pintype "passive"))
      (node (ref "P2") (pin "2") (pinfunction "2_2") (pintype "passive"))
      (node (ref "P2") (pin "3") (pinfunction "3_3") (pintype "passive"))
      (node (ref "P2") (pin "4") (pinfunction "4_4") (pintype "passive"))
      (node (ref "P4") (pin "4") (pinfunction "4_4") (pintype "passive"))
      (node (ref "R13") (pin "1") (pinfunction "1_1") (pintype "passive"))
      (node (ref "R18") (pin "2") (pinfunction "2_2") (pintype "passive"))
      (node (ref "R19") (pin "2") (pinfunction "2_2") (pintype "passive"))
      (node (ref "R2") (pin "1") (pinfunction "1_1") (pintype "passive"))
      (node (ref "R5") (pin "1") (pinfunction "1_1") (pintype "passive"))
      (node (ref "R9") (pin "1") (pinfunction "1_1") (pintype "passive"))
      (node (ref "S1") (pin "1") (pintype "passive"))
      (node (ref "S2") (pin "1") (pintype "passive"))
      (node (ref "TP49") (pin "1") (pinfunction "1_1") (pintype "passive"))
      (node (ref "TP50") (pin "1") (pinfunction "1_1") (pintype "passive"))
      (node (ref "TP51") (pin "1") (pinfunction "1_1") (pintype "passive"))
      (node (ref "U1") (pin "2") (pinfunction "GND_2") (pintype "power_in"))
      (node (ref "U2") (pin "17") (pinfunction "GND_17") (pintype "power_in"))
      (node (ref "U2") (pin "2") (pinfunction "GND_2") (pintype "power_in"))
      (node (ref "U2") (pin "46") (pinfunction "GND_46") (pintype "power_in"))
      (node (ref "U2") (pin "60") (pinfunction "GND_60") (pintype "power_in"))
      (node (ref "U3") (pin "2") (pinfunction "GND_2") (pintype "passive"))
      (node (ref "U4") (pin "6") (pinfunction "NC_6") (pintype "passive"))
      (node (ref "U4") (pin "7") (pinfunction "GND_7") (pintype "power_in"))
      (node (ref "U4") (pin "EPAD") (pinfunction "EPAD_EPAD") (pintype "passive"))
      (node (ref "U5") (pin "2") (pinfunction "GND_2") (pintype "passive"))
      (node (ref "U5") (pin "5") (pinfunction "DIR_5") (pintype "passive"))
      (node (ref "U6") (pin "13") (pinfunction "GND_13") (pintype "passive"))
      (node (ref "U6") (pin "17") (pinfunction "PAD_17") (pintype "passive"))
    )
    (net (code "38") (name "Net-(C14-Pad1)") (class "Default")
      (node (ref "C14") (pin "1") (pinfunction "1_1") (pintype "passive"))
      (node (ref "R5") (pin "2") (pinfunction "2_2") (pintype "passive"))
    )
    (net (code "39") (name "Net-(D2-K)") (class "Default")
      (node (ref "C16") (pin "1") (pinfunction "1_1") (pintype "passive"))
      (node (ref "D2") (pin "2") (pinfunction "K_2") (pintype "passive"))
      (node (ref "L2") (pin "1") (pintype "passive"))
      (node (ref "U4") (pin "8") (pinfunction "SW_8") (pintype "output"))
    )
    (net (code "40") (name "Net-(DL1-A)") (class "Default")
      (node (ref "DL1") (pin "2") (pinfunction "A_2") (pintype "passive"))
      (node (ref "R6") (pin "2") (pinfunction "2_2") (pintype "passive"))
    )
    (net (code "41") (name "Net-(DL2-A)") (class "Default")
      (node (ref "DL2") (pin "2") (pinfunction "A_2") (pintype "passive"))
      (node (ref "R7") (pin "2") (pinfunction "2_2") (pintype "passive"))
    )
    (net (code "42") (name "Net-(F1-Pad2)") (class "Default")
      (node (ref "F1") (pin "2") (pinfunction "2_2") (pintype "passive"))
      (node (ref "Q1") (pin "3") (pinfunction "3_3") (pintype "passive"))
    )
    (net (code "43") (name "Net-(H4-VBATT)") (class "Default")
      (node (ref "C17") (pin "2") (pintype "passive"))
      (node (ref "F1") (pin "1") (pinfunction "1_1") (pintype "passive"))
      (node (ref "H4") (pin "2") (pinfunction "VBATT_2") (pintype "passive"))
      (node (ref "TP13") (pin "1") (pinfunction "1_1") (pintype "passive"))
    )
    (net (code "44") (name "Net-(L3-Pad2)") (class "Default")
      (node (ref "L3") (pin "2") (pinfunction "2_2") (pintype "passive"))
      (node (ref "R10") (pin "1") (pinfunction "1_1") (pintype "passive"))
    )
    (net (code "45") (name "Net-(Q1-Pad1)") (class "Default")
      (node (ref "Q1") (pin "1") (pinfunction "1_1") (pintype "passive"))
      (node (ref "R13") (pin "2") (pinfunction "2_2") (pintype "passive"))
    )
    (net (code "46") (name "Net-(U1-EN)") (class "Default")
      (node (ref "C1") (pin "2") (pinfunction "2_2") (pintype "passive"))
      (node (ref "R14") (pin "2") (pinfunction "2_2") (pintype "passive"))
      (node (ref "U1") (pin "1") (pinfunction "IN_1") (pintype "power_in"))
      (node (ref "U1") (pin "3") (pinfunction "EN_3") (pintype "input"))
    )
    (net (code "47") (name "Net-(U2A-PB8{slash}XOUT)") (class "Default")
      (node (ref "C4") (pin "2") (pinfunction "2_2") (pintype "passive"))
      (node (ref "U2") (pin "61") (pinfunction "PB8/XOUT_61") (pintype "bidirectional"))
      (node (ref "Y1") (pin "1") (pinfunction "OSC1_1") (pintype "passive"))
    )
    (net (code "48") (name "Net-(U2A-PB9{slash}XIN)") (class "Default")
      (node (ref "C3") (pin "2") (pinfunction "2_2") (pintype "passive"))
      (node (ref "U2") (pin "62") (pinfunction "PB9/XIN_62") (pintype "bidirectional"))
      (node (ref "Y1") (pin "3") (pinfunction "OSC2_3") (pintype "passive"))
    )
    (net (code "49") (name "Net-(U2A-PB10{slash}DDM)") (class "Default")
      (node (ref "R4") (pin "2") (pinfunction "2_2") (pintype "passive"))
      (node (ref "U2") (pin "56") (pinfunction "PB10/DDM_56") (pintype "bidirectional"))
    )
    (net (code "50") (name "Net-(U2A-PB11{slash}DDP)") (class "Default")
      (node (ref "R3") (pin "2") (pinfunction "2_2") (pintype "passive"))
      (node (ref "U2") (pin "57") (pinfunction "PB11/DDP_57") (pintype "bidirectional"))
    )
    (net (code "51") (name "Net-(U2A-PB12{slash}ERASE)") (class "Default")
      (node (ref "TP4") (pin "1") (pinfunction "1_1") (pintype "passive"))
      (node (ref "U2") (pin "55") (pinfunction "PB12/ERASE_55") (pintype "bidirectional"))
    )
    (net (code "52") (name "Net-(U2B-ADVREF)") (class "Default")
      (node (ref "C11") (pin "2") (pinfunction "2_2") (pintype "passive"))
      (node (ref "C13") (pin "2") (pinfunction "2_2") (pintype "passive"))
      (node (ref "C5") (pin "2") (pinfunction "2_2") (pintype "passive"))
      (node (ref "C7") (pin "2") (pinfunction "2_2") (pintype "passive"))
      (node (ref "C9") (pin "2") (pinfunction "2_2") (pintype "passive"))
      (node (ref "R11") (pin "1") (pinfunction "1_1") (pintype "passive"))
      (node (ref "U2") (pin "1") (pinfunction "ADVREF_1") (pintype "input"))
      (node (ref "U2") (pin "18") (pinfunction "VDDIO_18") (pintype "power_in"))
      (node (ref "U2") (pin "45") (pinfunction "VDDIO_45") (pintype "power_in"))
      (node (ref "U2") (pin "58") (pinfunction "VDDIO_58") (pintype "power_in"))
      (node (ref "U2") (pin "7") (pinfunction "VDDIN_7") (pintype "power_in"))
    )
    (net (code "53") (name "Net-(U2B-VDDOUT)") (class "Default")
      (node (ref "C10") (pin "2") (pinfunction "2_2") (pintype "passive"))
      (node (ref "C12") (pin "2") (pinfunction "2_2") (pintype "passive"))
      (node (ref "C6") (pin "2") (pinfunction "2_2") (pintype "passive"))
      (node (ref "C8") (pin "2") (pinfunction "2_2") (pintype "passive"))
      (node (ref "L1") (pin "2") (pinfunction "2_2") (pintype "passive"))
      (node (ref "TP2") (pin "1") (pinfunction "1_1") (pintype "passive"))
      (node (ref "U2") (pin "12") (pinfunction "VDDCORE_12") (pintype "power_in"))
      (node (ref "U2") (pin "24") (pinfunction "VDDCORE_24") (pintype "power_in"))
      (node (ref "U2") (pin "54") (pinfunction "VDDCORE_54") (pintype "power_in"))
      (node (ref "U2") (pin "8") (pinfunction "VDDOUT_8") (pintype "power_in"))
    )
    (net (code "54") (name "Net-(U2B-VDDPLL)") (class "Default")
      (node (ref "C14") (pin "2") (pinfunction "2_2") (pintype "passive"))
      (node (ref "C15") (pin "1") (pinfunction "1_1") (pintype "passive"))
      (node (ref "L1") (pin "1") (pinfunction "1_1") (pintype "passive"))
      (node (ref "TP5") (pin "1") (pinfunction "1_1") (pintype "passive"))
      (node (ref "U2") (pin "64") (pinfunction "VDDPLL_64") (pintype "power_in"))
    )
    (net (code "55") (name "Net-(U3-VCC)") (class "Default")
      (node (ref "C18") (pin "2") (pinfunction "2_2") (pintype "passive"))
      (node (ref "L3") (pin "1") (pinfunction "1_1") (pintype "passive"))
      (node (ref "U3") (pin "1") (pinfunction "VCC_1") (pintype "passive"))
    )
    (net (code "56") (name "Net-(U4-BST)") (class "Default")
      (node (ref "C16") (pin "2") (pinfunction "2_2") (pintype "passive"))
      (node (ref "U4") (pin "1") (pinfunction "BST_1") (pintype "passive"))
    )
    (net (code "57") (name "Net-(U4-EN)") (class "Default")
      (node (ref "R12") (pin "2") (pinfunction "2_2") (pintype "passive"))
      (node (ref "U4") (pin "2") (pinfunction "VIN_2") (pintype "input"))
      (node (ref "U4") (pin "3") (pinfunction "EN_3") (pintype "input"))
    )
    (net (code "58") (name "Net-(U5-VCCA)") (class "Default")
      (node (ref "C19") (pin "2") (pinfunction "2_2") (pintype "passive"))
      (node (ref "R15") (pin "2") (pinfunction "2_2") (pintype "passive"))
      (node (ref "U5") (pin "1") (pinfunction "VCCA_1") (pintype "passive"))
    )
    (net (code "59") (name "Net-(U5-VCCB)") (class "Default")
      (node (ref "C20") (pin "2") (pinfunction "2_2") (pintype "passive"))
      (node (ref "R16") (pin "1") (pinfunction "1_1") (pintype "passive"))
      (node (ref "U5") (pin "6") (pinfunction "VCCB_6") (pintype "passive"))
    )
    (net (code "60") (name "Net-(U6-AISEN)") (class "Default")
      (node (ref "R18") (pin "1") (pinfunction "1_1") (pintype "passive"))
      (node (ref "U6") (pin "3") (pinfunction "AISEN_3") (pintype "passive"))
    )
    (net (code "61") (name "Net-(U6-AOUT1)") (class "Default")
      (node (ref "H8") (pin "2") (pintype "passive"))
      (node (ref "TP31") (pin "1") (pinfunction "1_1") (pintype "passive"))
      (node (ref "U6") (pin "2") (pinfunction "AOUT1_2") (pintype "passive"))
    )
    (net (code "62") (name "Net-(U6-AOUT2)") (class "Default")
      (node (ref "H8") (pin "1") (pintype "passive"))
      (node (ref "TP41") (pin "1") (pinfunction "1_1") (pintype "passive"))
      (node (ref "U6") (pin "4") (pinfunction "AOUT2_4") (pintype "passive"))
    )
    (net (code "63") (name "Net-(U6-BISEN)") (class "Default")
      (node (ref "R19") (pin "1") (pinfunction "1_1") (pintype "passive"))
      (node (ref "U6") (pin "6") (pinfunction "BISEN_6") (pintype "passive"))
    )
    (net (code "64") (name "Net-(U6-BOUT1)") (class "Default")
      (node (ref "H9") (pin "1") (pintype "passive"))
      (node (ref "TP34") (pin "1") (pinfunction "1_1") (pintype "passive"))
      (node (ref "U6") (pin "7") (pinfunction "BOUT1_7") (pintype "passive"))
    )
    (net (code "65") (name "Net-(U6-BOUT2)") (class "Default")
      (node (ref "H9") (pin "2") (pintype "passive"))
      (node (ref "TP42") (pin "1") (pinfunction "1_1") (pintype "passive"))
      (node (ref "U6") (pin "5") (pinfunction "BOUT2_5") (pintype "passive"))
    )
    (net (code "66") (name "Net-(U6-VCP)") (class "Default")
      (node (ref "C25") (pin "1") (pinfunction "1_1") (pintype "passive"))
      (node (ref "U6") (pin "11") (pinfunction "VCP_11") (pintype "passive"))
    )
    (net (code "67") (name "Net-(U6-VINT)") (class "Default")
      (node (ref "C26") (pin "1") (pinfunction "1_1") (pintype "passive"))
      (node (ref "U6") (pin "14") (pinfunction "VINT_14") (pintype "passive"))
    )
    (net (code "68") (name "Net-(U6-VM)") (class "Default")
      (node (ref "C24") (pin "2") (pinfunction "2_2") (pintype "passive"))
      (node (ref "C25") (pin "2") (pinfunction "2_2") (pintype "passive"))
      (node (ref "R17") (pin "1") (pinfunction "1_1") (pintype "passive"))
      (node (ref "U6") (pin "12") (pinfunction "VM_12") (pintype "passive"))
    )
    (net (code "69") (name "VBAT") (class "Default")
      (node (ref "Q1") (pin "2") (pinfunction "2_2") (pintype "passive"))
      (node (ref "R12") (pin "1") (pinfunction "1_1") (pintype "passive"))
      (node (ref "R17") (pin "2") (pinfunction "2_2") (pintype "passive"))
      (node (ref "R8") (pin "2") (pinfunction "2_2") (pintype "passive"))
    )
    (net (code "70") (name "VBUS") (class "Default")
      (node (ref "H1") (pin "1") (pinfunction "VBUS_1") (pintype "power_in"))
      (node (ref "R1") (pin "2") (pinfunction "2_2") (pintype "passive"))
      (node (ref "TP6") (pin "1") (pinfunction "1_1") (pintype "passive"))
    )
    (net (code "71") (name "unconnected-(C21-Pad2)") (class "Default")
      (node (ref "C21") (pin "2") (pinfunction "2_2") (pintype "passive"))
    )
    (net (code "72") (name "unconnected-(H1-ID-Pad4)") (class "Default")
      (node (ref "H1") (pin "4") (pinfunction "ID_4") (pintype "power_in+no_connect"))
    )
    (net (code "73") (name "unconnected-(H2-Pad3)") (class "Default")
      (node (ref "H2") (pin "3") (pinfunction "3_3") (pintype "passive+no_connect"))
    )
    (net (code "74") (name "unconnected-(H2-Pad9)") (class "Default")
      (node (ref "H2") (pin "9") (pinfunction "9_9") (pintype "passive+no_connect"))
    )
    (net (code "75") (name "unconnected-(H2-Pad10)") (class "Default")
      (node (ref "H2") (pin "10") (pinfunction "10_10") (pintype "passive+no_connect"))
    )
    (net (code "76") (name "unconnected-(U1-BYP-Pad4)") (class "Default")
      (node (ref "U1") (pin "4") (pinfunction "BYP_4") (pintype "passive+no_connect"))
    )
    (net (code "77") (name "unconnected-(U2A-JTAGSEL-Pad50)") (class "Default")
      (node (ref "U2") (pin "50") (pinfunction "JTAGSEL_50") (pintype "input+no_connect"))
    )
    (net (code "78") (name "unconnected-(U2A-PA8-Pad31)") (class "Default")
      (node (ref "U2") (pin "31") (pinfunction "PA8_31") (pintype "bidirectional+no_connect"))
    )
    (net (code "79") (name "unconnected-(U2A-PA28-Pad38)") (class "Default")
      (node (ref "U2") (pin "38") (pinfunction "PA28_38") (pintype "bidirectional+no_connect"))
    )
    (net (code "80") (name "unconnected-(U2A-PA29-Pad41)") (class "Default")
      (node (ref "U2") (pin "41") (pinfunction "PA29_41") (pintype "bidirectional+no_connect"))
    )
    (net (code "81") (name "unconnected-(U2A-PA31-Pad52)") (class "Default")
      (node (ref "U2") (pin "52") (pinfunction "PA31_52") (pintype "bidirectional+no_connect"))
    )
    (net (code "82") (name "unconnected-(U2A-PB1{slash}PWMH1{slash}AD5-Pad4)") (class "Default")
      (node (ref "U2") (pin "4") (pinfunction "PB1/PWMH1/AD5_4") (pintype "bidirectional+no_connect"))
    )
    (net (code "83") (name "unconnected-(U2A-PB5{slash}PWML0{slash}TDO-Pad49)") (class "Default")
      (node (ref "U2") (pin "49") (pinfunction "PB5/PWML0/TDO_49") (pintype "bidirectional+no_connect"))
    )
    (net (code "84") (name "unconnected-(U2A-PB13{slash}PWML2{slash}DAC0-Pad59)") (class "Default")
      (node (ref "U2") (pin "59") (pinfunction "PB13/PWML2/DAC0_59") (pintype "bidirectional+no_connect"))
    )
    (net (code "85") (name "unconnected-(U2A-PWMH1{slash}PA1-Pad47)") (class "Default")
      (node (ref "U2") (pin "47") (pinfunction "PWMH1/PA1_47") (pintype "bidirectional+no_connect"))
    )
    (net (code "86") (name "unconnected-(U2A-PWMH1{slash}PA24-Pad23)") (class "Default")
      (node (ref "U2") (pin "23") (pinfunction "PWMH1/PA24_23") (pintype "bidirectional+no_connect"))
    )
    (net (code "87") (name "unconnected-(U2A-PWMH2{slash}PA25-Pad25)") (class "Default")
      (node (ref "U2") (pin "25") (pinfunction "PWMH2/PA25_25") (pintype "bidirectional+no_connect"))
    )
    (net (code "88") (name "unconnected-(U2A-PWML2{slash}PA30-Pad42)") (class "Default")
      (node (ref "U2") (pin "42") (pinfunction "PWML2/PA30_42") (pintype "bidirectional+no_connect"))
    )
    (net (code "89") (name "unconnected-(U2A-TST-Pad40)") (class "Default")
      (node (ref "U2") (pin "40") (pinfunction "TST_40") (pintype "input+no_connect"))
    )
    (net (code "90") (name "unconnected-(U2A-TWD0{slash}PA3-Pad43)") (class "Default")
      (node (ref "U2") (pin "43") (pinfunction "TWD0/PA3_43") (pintype "bidirectional+no_connect"))
    )
    (net (code "91") (name "unconnected-(U4-PGOOD-Pad4)") (class "Default")
      (node (ref "U4") (pin "4") (pinfunction "PGOOD_4") (pintype "output+no_connect"))
    )
  )
)
